# Searchlight_Controller_V3_4.net
KiCad netlist of a schematic drawn in EAGLE
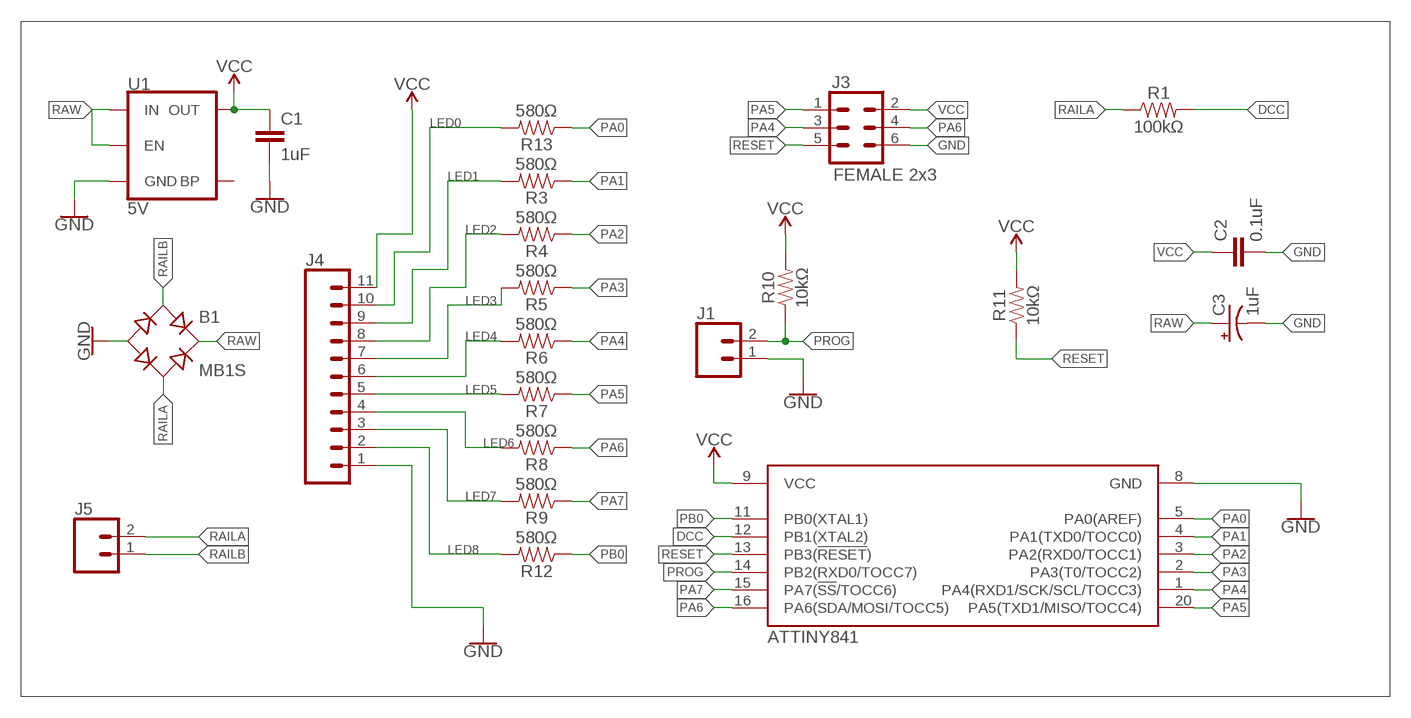
[diagram p0: schematic, sheet 1]

(export (version "E")
  (design (tool "Eeschema 10.0.6"))
  (components
    (comp (ref "B1")
      (value "MB1S")
      (footprint "eagle-import:SOIC-4")
      (libsource (lib "eagle-import") (part "MBS1"))
    )
    (comp (ref "C1")
      (value "1uF")
      (footprint "eagle-import:0603")
      (libsource (lib "eagle-import") (part "0.1UF-0603-25V-5%"))
    )
    (comp (ref "C2")
      (value "0.1uF")
      (footprint "eagle-import:0603")
      (libsource (lib "eagle-import") (part "0.1UF-0603-25V-5%"))
    )
    (comp (ref "C3")
      (value "1uF")
      (footprint "eagle-import:EIA3216")
      (libsource (lib "eagle-import") (part "10UF-POLAR-EIA3216-16V-10%(TANT)"))
    )
    (comp (ref "J1")
      (value "CONN_02LOCK")
      (footprint "eagle-import:1X02_LOCK")
      (libsource (lib "eagle-import") (part "CONN_02LOCK"))
    )
    (comp (ref "J3")
      (value "FEMALE 2x3")
      (footprint "eagle-import:2X3")
      (libsource (lib "eagle-import") (part "CONN_03X2FEMALE"))
    )
    (comp (ref "J4")
      (value "CONN_11LONGPADS")
      (footprint "eagle-import:1X11_LONGPADS")
      (libsource (lib "eagle-import") (part "CONN_11LONGPADS"))
    )
    (comp (ref "J5")
      (value "CONN_02")
      (footprint "eagle-import:1X02")
      (libsource (lib "eagle-import") (part "CONN_02"))
    )
    (comp (ref "R1")
      (value "100kΩ")
      (footprint "eagle-import:0603")
      (libsource (lib "eagle-import") (part "RESISTOR0603"))
    )
    (comp (ref "R3")
      (value "580Ω")
      (footprint "eagle-import:0603")
      (libsource (lib "eagle-import") (part "RESISTOR0603"))
    )
    (comp (ref "R4")
      (value "580Ω")
      (footprint "eagle-import:0603")
      (libsource (lib "eagle-import") (part "RESISTOR0603"))
    )
    (comp (ref "R5")
      (value "580Ω")
      (footprint "eagle-import:0603")
      (libsource (lib "eagle-import") (part "RESISTOR0603"))
    )
    (comp (ref "R6")
      (value "580Ω")
      (footprint "eagle-import:0603")
      (libsource (lib "eagle-import") (part "RESISTOR0603"))
    )
    (comp (ref "R7")
      (value "580Ω")
      (footprint "eagle-import:0603")
      (libsource (lib "eagle-import") (part "RESISTOR0603"))
    )
    (comp (ref "R8")
      (value "580Ω")
      (footprint "eagle-import:0603")
      (libsource (lib "eagle-import") (part "RESISTOR0603"))
    )
    (comp (ref "R9")
      (value "580Ω")
      (footprint "eagle-import:0603")
      (libsource (lib "eagle-import") (part "RESISTOR0603"))
    )
    (comp (ref "R10")
      (value "10kΩ")
      (footprint "eagle-import:0603")
      (libsource (lib "eagle-import") (part "RESISTOR0603"))
    )
    (comp (ref "R11")
      (value "10kΩ")
      (footprint "eagle-import:0603")
      (libsource (lib "eagle-import") (part "RESISTOR0603"))
    )
    (comp (ref "R12")
      (value "580Ω")
      (footprint "eagle-import:0603")
      (libsource (lib "eagle-import") (part "RESISTOR0603"))
    )
    (comp (ref "R13")
      (value "580Ω")
      (footprint "eagle-import:0603")
      (libsource (lib "eagle-import") (part "RESISTOR0603"))
    )
    (comp (ref "U$1")
      (value "ATTINY841-MMH")
      (footprint "eagle-import:QFN-20-4X4MM")
      (libsource (lib "eagle-import") (part "ATTINY841-MMH"))
    )
    (comp (ref "U1")
      (value "5V")
      (footprint "eagle-import:SOT23-5")
      (libsource (lib "eagle-import") (part "V_REG_MIC52055V"))
    )
  )
  (nets
    (net (code "1") (name "/LED0") (class "Default")
      (node (ref "J4") (pin "10") (pinfunction "10_10") (pintype "passive"))
      (node (ref "R13") (pin "2") (pinfunction "2_2") (pintype "passive"))
    )
    (net (code "2") (name "/LED1") (class "Default")
      (node (ref "J4") (pin "9") (pinfunction "9_9") (pintype "passive"))
      (node (ref "R3") (pin "2") (pinfunction "2_2") (pintype "passive"))
    )
    (net (code "3") (name "/LED2") (class "Default")
      (node (ref "J4") (pin "8") (pinfunction "8_8") (pintype "passive"))
      (node (ref "R4") (pin "2") (pinfunction "2_2") (pintype "passive"))
    )
    (net (code "4") (name "/LED3") (class "Default")
      (node (ref "J4") (pin "7") (pinfunction "7_7") (pintype "passive"))
      (node (ref "R5") (pin "2") (pinfunction "2_2") (pintype "passive"))
    )
    (net (code "5") (name "/LED4") (class "Default")
      (node (ref "J4") (pin "6") (pinfunction "6_6") (pintype "passive"))
      (node (ref "R6") (pin "2") (pinfunction "2_2") (pintype "passive"))
    )
    (net (code "6") (name "/LED5") (class "Default")
      (node (ref "J4") (pin "5") (pinfunction "5_5") (pintype "passive"))
      (node (ref "R7") (pin "2") (pinfunction "2_2") (pintype "passive"))
    )
    (net (code "7") (name "/LED6") (class "Default")
      (node (ref "J4") (pin "4") (pinfunction "4_4") (pintype "passive"))
      (node (ref "R8") (pin "2") (pinfunction "2_2") (pintype "passive"))
    )
    (net (code "8") (name "/LED7") (class "Default")
      (node (ref "J4") (pin "3") (pinfunction "3_3") (pintype "passive"))
      (node (ref "R9") (pin "2") (pinfunction "2_2") (pintype "passive"))
    )
    (net (code "9") (name "/LED8") (class "Default")
      (node (ref "J4") (pin "2") (pinfunction "2_2") (pintype "passive"))
      (node (ref "R12") (pin "2") (pinfunction "2_2") (pintype "passive"))
    )
    (net (code "10") (name "DCC") (class "Default")
      (node (ref "R1") (pin "2") (pinfunction "2_2") (pintype "passive"))
      (node (ref "U$1") (pin "12") (pinfunction "PB1(XTAL2)_12") (pintype "bidirectional"))
    )
    (net (code "11") (name "GND") (class "Default")
      (node (ref "B1") (pin "-") (pinfunction "-_-") (pintype "passive"))
      (node (ref "C1") (pin "2") (pinfunction "2_2") (pintype "passive"))
      (node (ref "C2") (pin "2") (pinfunction "2_2") (pintype "passive"))
      (node (ref "C3") (pin "-") (pinfunction "-_-") (pintype "passive"))
      (node (ref "J1") (pin "1") (pinfunction "1_1") (pintype "passive"))
      (node (ref "J3") (pin "6") (pinfunction "6_6") (pintype "bidirectional"))
      (node (ref "J4") (pin "1") (pinfunction "1_1") (pintype "passive"))
      (node (ref "U$1") (pin "8") (pinfunction "GND_8") (pintype "bidirectional"))
      (node (ref "U1") (pin "2") (pinfunction "GND_2") (pintype "input"))
    )
    (net (code "12") (name "PA0") (class "Default")
      (node (ref "R13") (pin "1") (pinfunction "1_1") (pintype "passive"))
      (node (ref "U$1") (pin "5") (pinfunction "PA0(AREF)_5") (pintype "bidirectional"))
    )
    (net (code "13") (name "PA1") (class "Default")
      (node (ref "R3") (pin "1") (pinfunction "1_1") (pintype "passive"))
      (node (ref "U$1") (pin "4") (pinfunction "PA1(TXD0/TOCC0)_4") (pintype "bidirectional"))
    )
    (net (code "14") (name "PA2") (class "Default")
      (node (ref "R4") (pin "1") (pinfunction "1_1") (pintype "passive"))
      (node (ref "U$1") (pin "3") (pinfunction "PA2(RXD0/TOCC1)_3") (pintype "bidirectional"))
    )
    (net (code "15") (name "PA3") (class "Default")
      (node (ref "R5") (pin "1") (pinfunction "1_1") (pintype "passive"))
      (node (ref "U$1") (pin "2") (pinfunction "PA3(T0/TOCC2)_2") (pintype "bidirectional"))
    )
    (net (code "16") (name "PA4") (class "Default")
      (node (ref "J3") (pin "3") (pinfunction "3_3") (pintype "bidirectional"))
      (node (ref "R6") (pin "1") (pinfunction "1_1") (pintype "passive"))
      (node (ref "U$1") (pin "1") (pinfunction "PA4(RXD1/SCK/SCL/TOCC3)_1") (pintype "bidirectional"))
    )
    (net (code "17") (name "PA5") (class "Default")
      (node (ref "J3") (pin "1") (pinfunction "1_1") (pintype "bidirectional"))
      (node (ref "R7") (pin "1") (pinfunction "1_1") (pintype "passive"))
      (node (ref "U$1") (pin "20") (pinfunction "PA5(TXD1/MISO/TOCC4)_20") (pintype "bidirectional"))
    )
    (net (code "18") (name "PA6") (class "Default")
      (node (ref "J3") (pin "4") (pinfunction "4_4") (pintype "bidirectional"))
      (node (ref "R8") (pin "1") (pinfunction "1_1") (pintype "passive"))
      (node (ref "U$1") (pin "16") (pinfunction "PA6(SDA/MOSI/TOCC5)_16") (pintype "bidirectional"))
    )
    (net (code "19") (name "PA7") (class "Default")
      (node (ref "R9") (pin "1") (pinfunction "1_1") (pintype "passive"))
      (node (ref "U$1") (pin "15") (pinfunction "PA7(~{SS}/TOCC6)_15") (pintype "bidirectional"))
    )
    (net (code "20") (name "PB0") (class "Default")
      (node (ref "R12") (pin "1") (pinfunction "1_1") (pintype "passive"))
      (node (ref "U$1") (pin "11") (pinfunction "PB0(XTAL1)_11") (pintype "bidirectional"))
    )
    (net (code "21") (name "PROG") (class "Default")
      (node (ref "J1") (pin "2") (pinfunction "2_2") (pintype "passive"))
      (node (ref "R10") (pin "1") (pinfunction "1_1") (pintype "passive"))
      (node (ref "U$1") (pin "14") (pinfunction "PB2(RXD0/TOCC7)_14") (pintype "bidirectional"))
    )
    (net (code "22") (name "RAILA") (class "Default")
      (node (ref "B1") (pin "~2") (pinfunction "AC2_~2") (pintype "passive"))
      (node (ref "J5") (pin "2") (pinfunction "2_2") (pintype "passive"))
      (node (ref "R1") (pin "1") (pinfunction "1_1") (pintype "passive"))
    )
    (net (code "23") (name "RAILB") (class "Default")
      (node (ref "B1") (pin "~1") (pinfunction "AC1_~1") (pintype "passive"))
      (node (ref "J5") (pin "1") (pinfunction "1_1") (pintype "passive"))
    )
    (net (code "24") (name "RAW") (class "Default")
      (node (ref "B1") (pin "+") (pinfunction "+_+") (pintype "passive"))
      (node (ref "C3") (pin "+") (pinfunction "+_+") (pintype "passive"))
      (node (ref "U1") (pin "1") (pinfunction "IN_1") (pintype "input"))
      (node (ref "U1") (pin "3") (pinfunction "EN_3") (pintype "input"))
    )
    (net (code "25") (name "RESET") (class "Default")
      (node (ref "J3") (pin "5") (pinfunction "5_5") (pintype "bidirectional"))
      (node (ref "R11") (pin "1") (pinfunction "1_1") (pintype "passive"))
      (node (ref "U$1") (pin "13") (pinfunction "PB3(~{RESET})_13") (pintype "bidirectional"))
    )
    (net (code "26") (name "VCC") (class "Default")
      (node (ref "C1") (pin "1") (pinfunction "1_1") (pintype "passive"))
      (node (ref "C2") (pin "1") (pinfunction "1_1") (pintype "passive"))
      (node (ref "J3") (pin "2") (pinfunction "2_2") (pintype "bidirectional"))
      (node (ref "J4") (pin "11") (pinfunction "11_11") (pintype "passive"))
      (node (ref "R10") (pin "2") (pinfunction "2_2") (pintype "passive"))
      (node (ref "R11") (pin "2") (pinfunction "2_2") (pintype "passive"))
      (node (ref "U$1") (pin "9") (pinfunction "VCC_9") (pintype "bidirectional"))
      (node (ref "U1") (pin "5") (pinfunction "OUT_5") (pintype "passive"))
    )
    (net (code "27") (name "unconnected-(U1-BP-Pad4)") (class "Default")
      (node (ref "U1") (pin "4") (pinfunction "BP_4") (pintype "input"))
    )
  )
)
